# bal2un_2.net
KiCad netlist of a schematic drawn in Altium Designer
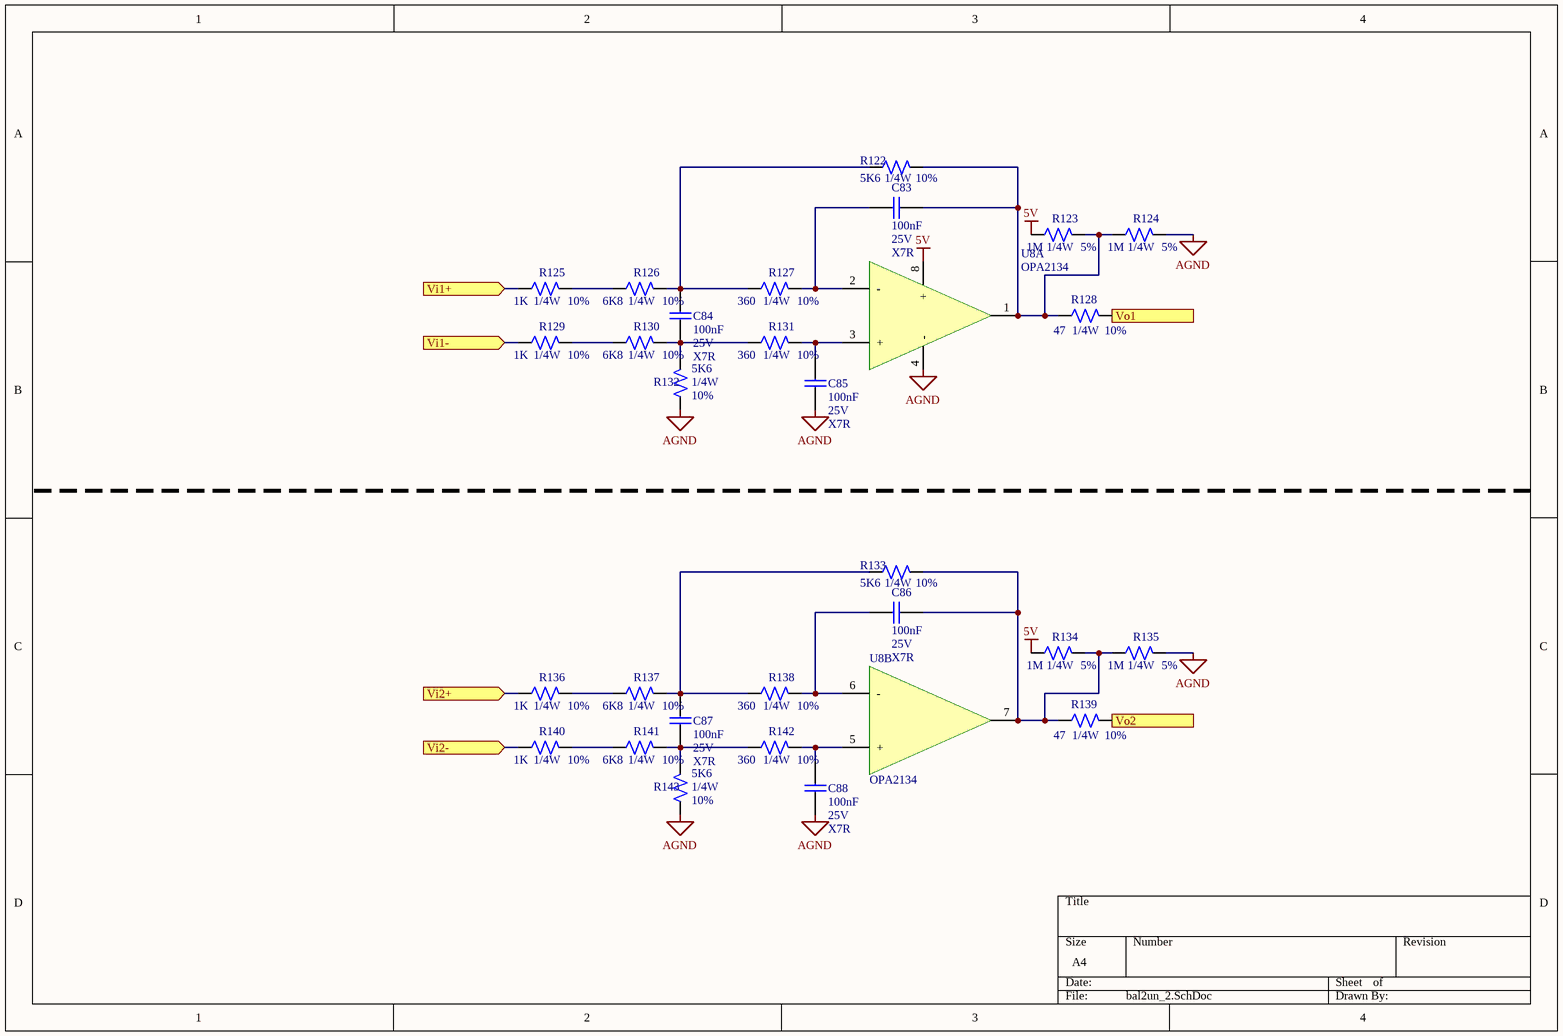
[diagram p0: bal2un_2.SchDoc]

(export (version "E")
  (design (tool "Eeschema 10.0.6"))
  (components
    (comp (ref "C83")
      (value "Capacitor")
      (footprint "C0805")
      (description "Capacitor de placas paralelas")
      (fields (field (name "VALOR") "100nF") (field (name "TENSION") "25V") (field (name "TOLERANCIA") "X7R"))
      (libsource (lib "Sch_Comunes") (part "Capacitor"))
    )
    (comp (ref "C84")
      (value "Capacitor")
      (footprint "C0805")
      (description "Capacitor de placas paralelas")
      (fields (field (name "VALOR") "100nF") (field (name "TENSION") "25V") (field (name "TOLERANCIA") "X7R"))
      (libsource (lib "Sch_Comunes") (part "Capacitor"))
    )
    (comp (ref "C85")
      (value "Capacitor")
      (footprint "C0805")
      (description "Capacitor de placas paralelas")
      (fields (field (name "VALOR") "100nF") (field (name "TENSION") "25V") (field (name "TOLERANCIA") "X7R"))
      (libsource (lib "Sch_Comunes") (part "Capacitor"))
    )
    (comp (ref "C86")
      (value "Capacitor")
      (footprint "C0805")
      (description "Capacitor de placas paralelas")
      (fields (field (name "VALOR") "100nF") (field (name "TENSION") "25V") (field (name "TOLERANCIA") "X7R"))
      (libsource (lib "Sch_Comunes") (part "Capacitor"))
    )
    (comp (ref "C87")
      (value "Capacitor")
      (footprint "C0805")
      (description "Capacitor de placas paralelas")
      (fields (field (name "VALOR") "100nF") (field (name "TENSION") "25V") (field (name "TOLERANCIA") "X7R"))
      (libsource (lib "Sch_Comunes") (part "Capacitor"))
    )
    (comp (ref "C88")
      (value "Capacitor")
      (footprint "C0805")
      (description "Capacitor de placas paralelas")
      (fields (field (name "VALOR") "100nF") (field (name "TENSION") "25V") (field (name "TOLERANCIA") "X7R"))
      (libsource (lib "Sch_Comunes") (part "Capacitor"))
    )
    (comp (ref "R122")
      (value "Resistor")
      (footprint "R0805")
      (description "Resistencia")
      (fields (field (name "VALOR") "5K6") (field (name "POTENCIA") "1/4W") (field (name "TOLERANCIA") "10%"))
      (libsource (lib "sch_comunes") (part "Resistor"))
    )
    (comp (ref "R123")
      (value "Resistor")
      (footprint "R0805")
      (description "Resistencia")
      (fields (field (name "VALOR") "1M") (field (name "POTENCIA") "1/4W") (field (name "TOLERANCIA") "5%"))
      (libsource (lib "sch_comunes") (part "Resistor"))
    )
    (comp (ref "R124")
      (value "Resistor")
      (footprint "R0805")
      (description "Resistencia")
      (fields (field (name "VALOR") "1M") (field (name "POTENCIA") "1/4W") (field (name "TOLERANCIA") "5%"))
      (libsource (lib "sch_comunes") (part "Resistor"))
    )
    (comp (ref "R125")
      (value "Resistor")
      (footprint "R0805")
      (description "Resistencia")
      (fields (field (name "VALOR") "1K") (field (name "POTENCIA") "1/4W") (field (name "TOLERANCIA") "10%"))
      (libsource (lib "sch_comunes") (part "Resistor"))
    )
    (comp (ref "R126")
      (value "Resistor")
      (footprint "R0805")
      (description "Resistencia")
      (fields (field (name "VALOR") "6K8") (field (name "POTENCIA") "1/4W") (field (name "TOLERANCIA") "10%"))
      (libsource (lib "sch_comunes") (part "Resistor"))
    )
    (comp (ref "R127")
      (value "Resistor")
      (footprint "R0805")
      (description "Resistencia")
      (fields (field (name "VALOR") "360") (field (name "POTENCIA") "1/4W") (field (name "TOLERANCIA") "10%"))
      (libsource (lib "sch_comunes") (part "Resistor"))
    )
    (comp (ref "R128")
      (value "Resistor")
      (footprint "R0805")
      (description "Resistencia")
      (fields (field (name "VALOR") "47") (field (name "POTENCIA") "1/4W") (field (name "TOLERANCIA") "10%"))
      (libsource (lib "sch_comunes") (part "Resistor"))
    )
    (comp (ref "R129")
      (value "Resistor")
      (footprint "R0805")
      (description "Resistencia")
      (fields (field (name "VALOR") "1K") (field (name "POTENCIA") "1/4W") (field (name "TOLERANCIA") "10%"))
      (libsource (lib "sch_comunes") (part "Resistor"))
    )
    (comp (ref "R130")
      (value "Resistor")
      (footprint "R0805")
      (description "Resistencia")
      (fields (field (name "VALOR") "6K8") (field (name "POTENCIA") "1/4W") (field (name "TOLERANCIA") "10%"))
      (libsource (lib "sch_comunes") (part "Resistor"))
    )
    (comp (ref "R131")
      (value "Resistor")
      (footprint "R0805")
      (description "Resistencia")
      (fields (field (name "VALOR") "360") (field (name "POTENCIA") "1/4W") (field (name "TOLERANCIA") "10%"))
      (libsource (lib "sch_comunes") (part "Resistor"))
    )
    (comp (ref "R132")
      (value "Resistor")
      (footprint "R0805")
      (description "Resistencia")
      (fields (field (name "VALOR") "5K6") (field (name "POTENCIA") "1/4W") (field (name "TOLERANCIA") "10%"))
      (libsource (lib "sch_comunes") (part "Resistor"))
    )
    (comp (ref "R133")
      (value "Resistor")
      (footprint "R0805")
      (description "Resistencia")
      (fields (field (name "VALOR") "5K6") (field (name "POTENCIA") "1/4W") (field (name "TOLERANCIA") "10%"))
      (libsource (lib "sch_comunes") (part "Resistor"))
    )
    (comp (ref "R134")
      (value "Resistor")
      (footprint "R0805")
      (description "Resistencia")
      (fields (field (name "VALOR") "1M") (field (name "POTENCIA") "1/4W") (field (name "TOLERANCIA") "5%"))
      (libsource (lib "sch_comunes") (part "Resistor"))
    )
    (comp (ref "R135")
      (value "Resistor")
      (footprint "R0805")
      (description "Resistencia")
      (fields (field (name "VALOR") "1M") (field (name "POTENCIA") "1/4W") (field (name "TOLERANCIA") "5%"))
      (libsource (lib "sch_comunes") (part "Resistor"))
    )
    (comp (ref "R136")
      (value "Resistor")
      (footprint "R0805")
      (description "Resistencia")
      (fields (field (name "VALOR") "1K") (field (name "POTENCIA") "1/4W") (field (name "TOLERANCIA") "10%"))
      (libsource (lib "sch_comunes") (part "Resistor"))
    )
    (comp (ref "R137")
      (value "Resistor")
      (footprint "R0805")
      (description "Resistencia")
      (fields (field (name "VALOR") "6K8") (field (name "POTENCIA") "1/4W") (field (name "TOLERANCIA") "10%"))
      (libsource (lib "sch_comunes") (part "Resistor"))
    )
    (comp (ref "R138")
      (value "Resistor")
      (footprint "R0805")
      (description "Resistencia")
      (fields (field (name "VALOR") "360") (field (name "POTENCIA") "1/4W") (field (name "TOLERANCIA") "10%"))
      (libsource (lib "sch_comunes") (part "Resistor"))
    )
    (comp (ref "R139")
      (value "Resistor")
      (footprint "R0805")
      (description "Resistencia")
      (fields (field (name "VALOR") "47") (field (name "POTENCIA") "1/4W") (field (name "TOLERANCIA") "10%"))
      (libsource (lib "sch_comunes") (part "Resistor"))
    )
    (comp (ref "R140")
      (value "Resistor")
      (footprint "R0805")
      (description "Resistencia")
      (fields (field (name "VALOR") "1K") (field (name "POTENCIA") "1/4W") (field (name "TOLERANCIA") "10%"))
      (libsource (lib "sch_comunes") (part "Resistor"))
    )
    (comp (ref "R141")
      (value "Resistor")
      (footprint "R0805")
      (description "Resistencia")
      (fields (field (name "VALOR") "6K8") (field (name "POTENCIA") "1/4W") (field (name "TOLERANCIA") "10%"))
      (libsource (lib "sch_comunes") (part "Resistor"))
    )
    (comp (ref "R142")
      (value "Resistor")
      (footprint "R0805")
      (description "Resistencia")
      (fields (field (name "VALOR") "360") (field (name "POTENCIA") "1/4W") (field (name "TOLERANCIA") "10%"))
      (libsource (lib "sch_comunes") (part "Resistor"))
    )
    (comp (ref "R143")
      (value "Resistor")
      (footprint "R0805")
      (description "Resistencia")
      (fields (field (name "VALOR") "5K6") (field (name "POTENCIA") "1/4W") (field (name "TOLERANCIA") "10%"))
      (libsource (lib "sch_comunes") (part "Resistor"))
    )
    (comp (ref "U8")
      (value "OPA2134")
      (footprint "D8")
      (description "Integrado con 2 operacionales")
      (libsource (lib "sch_opamp") (part "Opamp_x2"))
    )
  )
  (nets
    (net (code "1") (name "/Vi1+") (class "Default")
      (node (ref "R125") (pin "1") (pinfunction "1_1") (pintype "passive"))
    )
    (net (code "2") (name "/Vi1-") (class "Default")
      (node (ref "R129") (pin "1") (pinfunction "1_1") (pintype "passive"))
    )
    (net (code "3") (name "/Vi2+") (class "Default")
      (node (ref "R136") (pin "1") (pinfunction "1_1") (pintype "passive"))
    )
    (net (code "4") (name "/Vi2-") (class "Default")
      (node (ref "R140") (pin "1") (pinfunction "1_1") (pintype "passive"))
    )
    (net (code "5") (name "/Vo1") (class "Default")
      (node (ref "R128") (pin "2") (pinfunction "2_2") (pintype "passive"))
    )
    (net (code "6") (name "/Vo2") (class "Default")
      (node (ref "R139") (pin "2") (pinfunction "2_2") (pintype "passive"))
    )
    (net (code "7") (name "5V") (class "Default")
      (node (ref "R123") (pin "1") (pinfunction "1_1") (pintype "passive"))
      (node (ref "R134") (pin "1") (pinfunction "1_1") (pintype "passive"))
      (node (ref "U8") (pin "8") (pinfunction "+_8") (pintype "power_in"))
    )
    (net (code "8") (name "AGND") (class "Default")
      (node (ref "C85") (pin "2") (pinfunction "2_2") (pintype "passive"))
      (node (ref "C88") (pin "2") (pinfunction "2_2") (pintype "passive"))
      (node (ref "R124") (pin "2") (pinfunction "2_2") (pintype "passive"))
      (node (ref "R132") (pin "1") (pinfunction "1_1") (pintype "passive"))
      (node (ref "R135") (pin "2") (pinfunction "2_2") (pintype "passive"))
      (node (ref "R143") (pin "1") (pinfunction "1_1") (pintype "passive"))
      (node (ref "U8") (pin "4") (pinfunction "-_4") (pintype "passive"))
    )
    (net (code "9") (name "Net-(C83-Pad2)") (class "Default")
      (node (ref "C83") (pin "2") (pinfunction "2_2") (pintype "passive"))
      (node (ref "R127") (pin "2") (pinfunction "2_2") (pintype "passive"))
      (node (ref "U8") (pin "2") (pinfunction "-_2") (pintype "passive"))
    )
    (net (code "10") (name "Net-(C84-Pad1)") (class "Default")
      (node (ref "C84") (pin "1") (pinfunction "1_1") (pintype "passive"))
      (node (ref "R122") (pin "1") (pinfunction "1_1") (pintype "passive"))
      (node (ref "R126") (pin "2") (pinfunction "2_2") (pintype "passive"))
      (node (ref "R127") (pin "1") (pinfunction "1_1") (pintype "passive"))
    )
    (net (code "11") (name "Net-(C84-Pad2)") (class "Default")
      (node (ref "C84") (pin "2") (pinfunction "2_2") (pintype "passive"))
      (node (ref "R130") (pin "2") (pinfunction "2_2") (pintype "passive"))
      (node (ref "R131") (pin "1") (pinfunction "1_1") (pintype "passive"))
      (node (ref "R132") (pin "2") (pinfunction "2_2") (pintype "passive"))
    )
    (net (code "12") (name "Net-(C85-Pad1)") (class "Default")
      (node (ref "C85") (pin "1") (pinfunction "1_1") (pintype "passive"))
      (node (ref "R131") (pin "2") (pinfunction "2_2") (pintype "passive"))
      (node (ref "U8") (pin "3") (pinfunction "+_3") (pintype "passive"))
    )
    (net (code "13") (name "Net-(C87-Pad1)") (class "Default")
      (node (ref "C87") (pin "1") (pinfunction "1_1") (pintype "passive"))
      (node (ref "R133") (pin "1") (pinfunction "1_1") (pintype "passive"))
      (node (ref "R137") (pin "2") (pinfunction "2_2") (pintype "passive"))
      (node (ref "R138") (pin "1") (pinfunction "1_1") (pintype "passive"))
    )
    (net (code "14") (name "Net-(C87-Pad2)") (class "Default")
      (node (ref "C87") (pin "2") (pinfunction "2_2") (pintype "passive"))
      (node (ref "R141") (pin "2") (pinfunction "2_2") (pintype "passive"))
      (node (ref "R142") (pin "1") (pinfunction "1_1") (pintype "passive"))
      (node (ref "R143") (pin "2") (pinfunction "2_2") (pintype "passive"))
    )
    (net (code "15") (name "Net-(R125-Pad2)") (class "Default")
      (node (ref "R125") (pin "2") (pinfunction "2_2") (pintype "passive"))
      (node (ref "R126") (pin "1") (pinfunction "1_1") (pintype "passive"))
    )
    (net (code "16") (name "Net-(R129-Pad2)") (class "Default")
      (node (ref "R129") (pin "2") (pinfunction "2_2") (pintype "passive"))
      (node (ref "R130") (pin "1") (pinfunction "1_1") (pintype "passive"))
    )
    (net (code "17") (name "Net-(R136-Pad2)") (class "Default")
      (node (ref "R136") (pin "2") (pinfunction "2_2") (pintype "passive"))
      (node (ref "R137") (pin "1") (pinfunction "1_1") (pintype "passive"))
    )
    (net (code "18") (name "Net-(R140-Pad2)") (class "Default")
      (node (ref "R140") (pin "2") (pinfunction "2_2") (pintype "passive"))
      (node (ref "R141") (pin "1") (pinfunction "1_1") (pintype "passive"))
    )
    (net (code "19") (name "Net-(U8A-OUT)") (class "Default")
      (node (ref "C83") (pin "1") (pinfunction "1_1") (pintype "passive"))
      (node (ref "R122") (pin "2") (pinfunction "2_2") (pintype "passive"))
      (node (ref "R123") (pin "2") (pinfunction "2_2") (pintype "passive"))
      (node (ref "R124") (pin "1") (pinfunction "1_1") (pintype "passive"))
      (node (ref "R128") (pin "1") (pinfunction "1_1") (pintype "passive"))
      (node (ref "U8") (pin "1") (pinfunction "OUT_1") (pintype "passive"))
    )
    (net (code "20") (name "Net-(U8B-+)") (class "Default")
      (node (ref "C88") (pin "1") (pinfunction "1_1") (pintype "passive"))
      (node (ref "R142") (pin "2") (pinfunction "2_2") (pintype "passive"))
      (node (ref "U8") (pin "5") (pinfunction "+_5") (pintype "passive"))
    )
    (net (code "21") (name "Net-(U8B--)") (class "Default")
      (node (ref "C86") (pin "2") (pinfunction "2_2") (pintype "passive"))
      (node (ref "R138") (pin "2") (pinfunction "2_2") (pintype "passive"))
      (node (ref "U8") (pin "6") (pinfunction "-_6") (pintype "passive"))
    )
    (net (code "22") (name "Net-(U8B-OUT)") (class "Default")
      (node (ref "C86") (pin "1") (pinfunction "1_1") (pintype "passive"))
      (node (ref "R133") (pin "2") (pinfunction "2_2") (pintype "passive"))
      (node (ref "R134") (pin "2") (pinfunction "2_2") (pintype "passive"))
      (node (ref "R135") (pin "1") (pinfunction "1_1") (pintype "passive"))
      (node (ref "R139") (pin "1") (pinfunction "1_1") (pintype "passive"))
      (node (ref "U8") (pin "7") (pinfunction "OUT_7") (pintype "passive"))
    )
  )
)
